# SD.net
KiCad netlist of a schematic drawn in Altium Designer
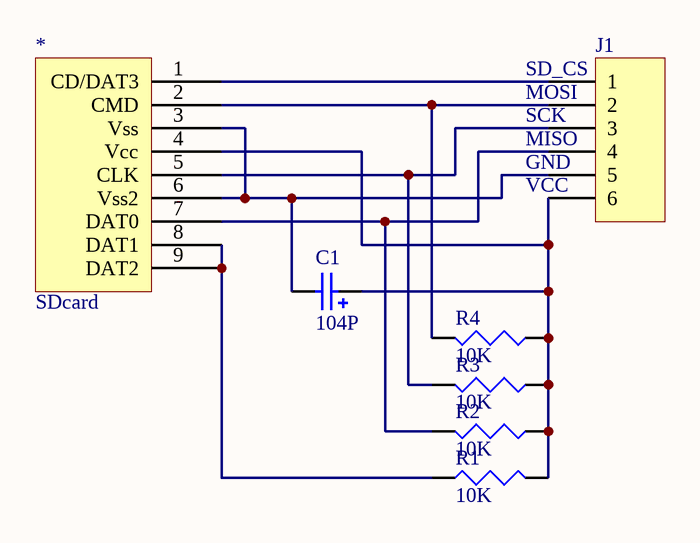
[diagram p0: SD.SchDoc]

(export (version "E")
  (design (tool "Eeschema 10.0.6"))
  (components
    (comp (ref "*") (value "SDcard") (footprint "SDcard") (libsource (lib "SDCARD") (part "SDcard")))
    (comp (ref "C1")
      (value "104P")
      (footprint "CC2012-0805")
      (description "Polarized Capacitor (Surface Mount)")
      (fields (field (name "Comment") "Cap Pol3") (field (name "PUBLISHER") "Altium Limited"))
      (libsource (lib "Miscellaneous Devices") (part "Cap Pol3"))
    )
    (comp (ref "J1")
      (value "Header 6")
      (footprint "HDR1X6")
      (description "Header, 6-Pin")
      (fields (field (name "PUBLISHER") "Altium Limited"))
      (libsource (lib "Miscellaneous Connectors") (part "Header 6"))
    )
    (comp (ref "R1")
      (value "10K")
      (footprint "R2012-0805")
      (description "Resistor")
      (fields (field (name "Comment") "Res3") (field (name "PUBLISHER") "Altium Limited"))
      (libsource (lib "Miscellaneous Devices") (part "Res3"))
    )
    (comp (ref "R2")
      (value "10K")
      (footprint "R2012-0805")
      (description "Resistor")
      (fields (field (name "Comment") "Res3") (field (name "PUBLISHER") "Altium Limited"))
      (libsource (lib "Miscellaneous Devices") (part "Res3"))
    )
    (comp (ref "R3")
      (value "10K")
      (footprint "R2012-0805")
      (description "Resistor")
      (fields (field (name "Comment") "Res3") (field (name "PUBLISHER") "Altium Limited"))
      (libsource (lib "Miscellaneous Devices") (part "Res3"))
    )
    (comp (ref "R4")
      (value "10K")
      (footprint "R2012-0805")
      (description "Resistor")
      (fields (field (name "Comment") "Res3") (field (name "PUBLISHER") "Altium Limited"))
      (libsource (lib "Miscellaneous Devices") (part "Res3"))
    )
  )
  (nets
    (net (code "1") (name "Net-(*-CD{slash}DAT3)") (class "Default")
      (node (ref "*") (pin "1") (pinfunction "CD/DAT3_1") (pintype "passive"))
      (node (ref "J1") (pin "1") (pinfunction "1_1") (pintype "passive"))
    )
    (net (code "2") (name "Net-(*-CLK)") (class "Default")
      (node (ref "*") (pin "5") (pinfunction "CLK_5") (pintype "passive"))
      (node (ref "J1") (pin "3") (pinfunction "3_3") (pintype "passive"))
      (node (ref "R3") (pin "2") (pinfunction "2_2") (pintype "passive"))
    )
    (net (code "3") (name "Net-(*-CMD)") (class "Default")
      (node (ref "*") (pin "2") (pinfunction "CMD_2") (pintype "passive"))
      (node (ref "J1") (pin "2") (pinfunction "2_2") (pintype "passive"))
      (node (ref "R4") (pin "2") (pinfunction "2_2") (pintype "passive"))
    )
    (net (code "4") (name "Net-(*-DAT0)") (class "Default")
      (node (ref "*") (pin "7") (pinfunction "DAT0_7") (pintype "passive"))
      (node (ref "J1") (pin "4") (pinfunction "4_4") (pintype "passive"))
      (node (ref "R2") (pin "2") (pinfunction "2_2") (pintype "passive"))
    )
    (net (code "5") (name "Net-(*-DAT1)") (class "Default")
      (node (ref "*") (pin "8") (pinfunction "DAT1_8") (pintype "passive"))
      (node (ref "*") (pin "9") (pinfunction "DAT2_9") (pintype "passive"))
      (node (ref "R1") (pin "1") (pinfunction "1_1") (pintype "passive"))
    )
    (net (code "6") (name "Net-(*-Vcc)") (class "Default")
      (node (ref "*") (pin "4") (pinfunction "Vcc_4") (pintype "passive"))
      (node (ref "C1") (pin "1") (pinfunction "1_1") (pintype "passive"))
      (node (ref "J1") (pin "6") (pinfunction "6_6") (pintype "passive"))
      (node (ref "R1") (pin "2") (pinfunction "2_2") (pintype "passive"))
      (node (ref "R2") (pin "1") (pinfunction "1_1") (pintype "passive"))
      (node (ref "R3") (pin "1") (pinfunction "1_1") (pintype "passive"))
      (node (ref "R4") (pin "1") (pinfunction "1_1") (pintype "passive"))
    )
    (net (code "7") (name "Net-(*-Vss)") (class "Default")
      (node (ref "*") (pin "3") (pinfunction "Vss_3") (pintype "passive"))
      (node (ref "*") (pin "6") (pinfunction "Vss2_6") (pintype "passive"))
      (node (ref "C1") (pin "2") (pinfunction "2_2") (pintype "passive"))
      (node (ref "J1") (pin "5") (pinfunction "5_5") (pintype "passive"))
    )
  )
)
